# WS2812B.net
KiCad netlist of a schematic drawn in Altium Designer
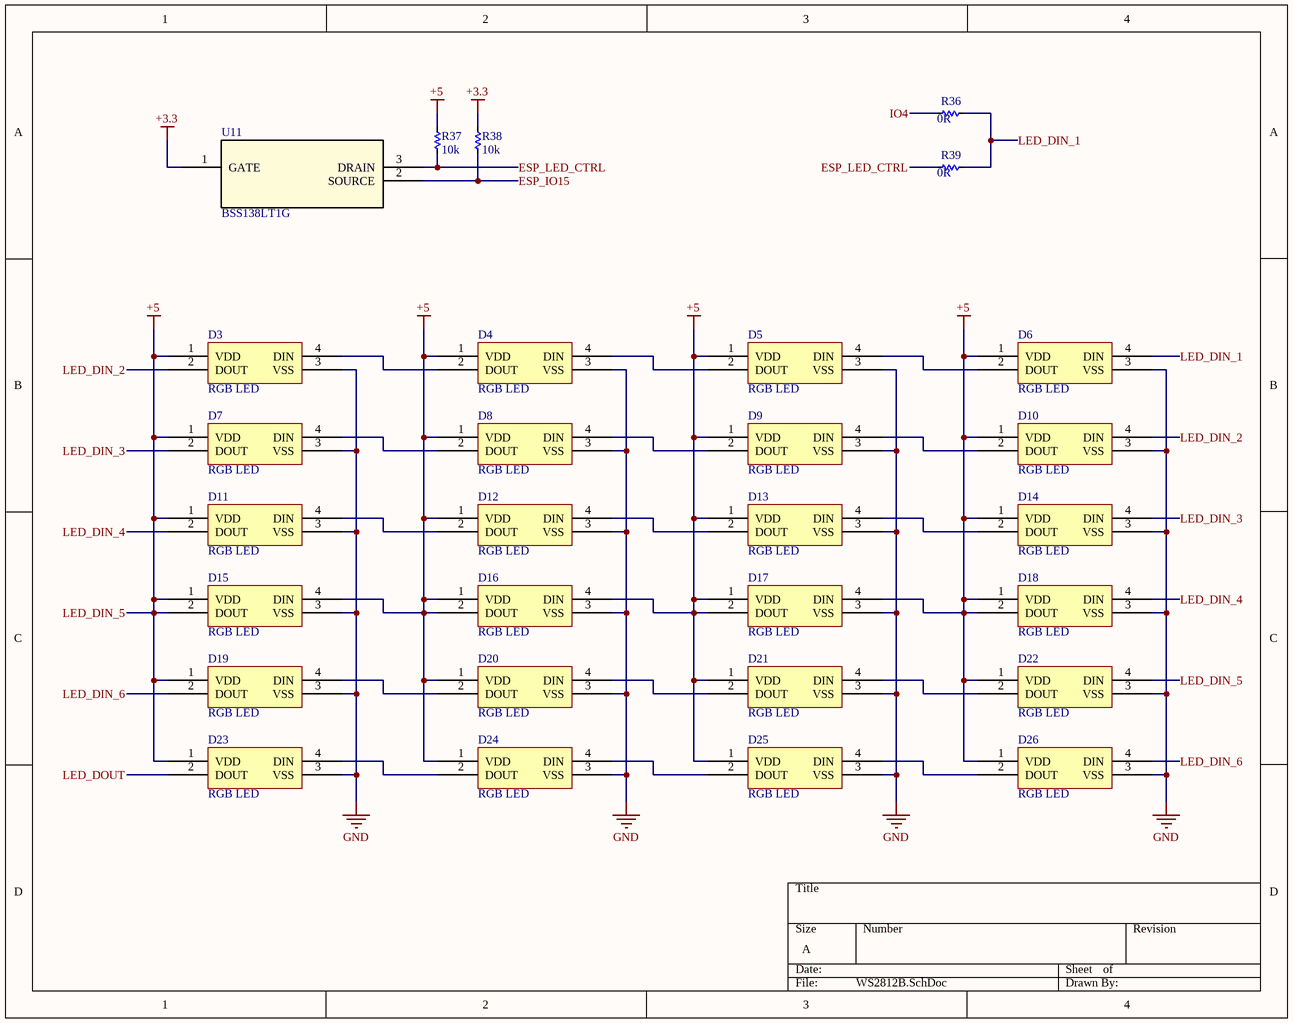
[diagram p0: WS2812B.SchDoc]

(export (version "E")
  (design (tool "Eeschema 10.0.6"))
  (components
    (comp (ref "D3")
      (value "RGB LED")
      (footprint "WS2812B")
      (description "RGB 620~630nm Red, 515~530nm Green, 465~475nm Blue SMD,5x5mm Light Emitting Diodes (LED) ROHS")
      (fields (field (name "MANUFACTURER") "Worldsemi"))
      (libsource (lib "WS2812B") (part "WS2812B"))
    )
    (comp (ref "D4")
      (value "RGB LED")
      (footprint "WS2812B")
      (description "RGB 620~630nm Red, 515~530nm Green, 465~475nm Blue SMD,5x5mm Light Emitting Diodes (LED) ROHS")
      (fields (field (name "MANUFACTURER") "Worldsemi"))
      (libsource (lib "WS2812B") (part "WS2812B"))
    )
    (comp (ref "D5")
      (value "RGB LED")
      (footprint "WS2812B")
      (description "RGB 620~630nm Red, 515~530nm Green, 465~475nm Blue SMD,5x5mm Light Emitting Diodes (LED) ROHS")
      (fields (field (name "MANUFACTURER") "Worldsemi"))
      (libsource (lib "WS2812B") (part "WS2812B"))
    )
    (comp (ref "D6")
      (value "RGB LED")
      (footprint "WS2812B")
      (description "RGB 620~630nm Red, 515~530nm Green, 465~475nm Blue SMD,5x5mm Light Emitting Diodes (LED) ROHS")
      (fields (field (name "MANUFACTURER") "Worldsemi"))
      (libsource (lib "WS2812B") (part "WS2812B"))
    )
    (comp (ref "D7")
      (value "RGB LED")
      (footprint "WS2812B")
      (description "RGB 620~630nm Red, 515~530nm Green, 465~475nm Blue SMD,5x5mm Light Emitting Diodes (LED) ROHS")
      (fields (field (name "MANUFACTURER") "Worldsemi"))
      (libsource (lib "WS2812B") (part "WS2812B"))
    )
    (comp (ref "D8")
      (value "RGB LED")
      (footprint "WS2812B")
      (description "RGB 620~630nm Red, 515~530nm Green, 465~475nm Blue SMD,5x5mm Light Emitting Diodes (LED) ROHS")
      (fields (field (name "MANUFACTURER") "Worldsemi"))
      (libsource (lib "WS2812B") (part "WS2812B"))
    )
    (comp (ref "D9")
      (value "RGB LED")
      (footprint "WS2812B")
      (description "RGB 620~630nm Red, 515~530nm Green, 465~475nm Blue SMD,5x5mm Light Emitting Diodes (LED) ROHS")
      (fields (field (name "MANUFACTURER") "Worldsemi"))
      (libsource (lib "WS2812B") (part "WS2812B"))
    )
    (comp (ref "D10")
      (value "RGB LED")
      (footprint "WS2812B")
      (description "RGB 620~630nm Red, 515~530nm Green, 465~475nm Blue SMD,5x5mm Light Emitting Diodes (LED) ROHS")
      (fields (field (name "MANUFACTURER") "Worldsemi"))
      (libsource (lib "WS2812B") (part "WS2812B"))
    )
    (comp (ref "D11")
      (value "RGB LED")
      (footprint "WS2812B")
      (description "RGB 620~630nm Red, 515~530nm Green, 465~475nm Blue SMD,5x5mm Light Emitting Diodes (LED) ROHS")
      (fields (field (name "MANUFACTURER") "Worldsemi"))
      (libsource (lib "WS2812B") (part "WS2812B"))
    )
    (comp (ref "D12")
      (value "RGB LED")
      (footprint "WS2812B")
      (description "RGB 620~630nm Red, 515~530nm Green, 465~475nm Blue SMD,5x5mm Light Emitting Diodes (LED) ROHS")
      (fields (field (name "MANUFACTURER") "Worldsemi"))
      (libsource (lib "WS2812B") (part "WS2812B"))
    )
    (comp (ref "D13")
      (value "RGB LED")
      (footprint "WS2812B")
      (description "RGB 620~630nm Red, 515~530nm Green, 465~475nm Blue SMD,5x5mm Light Emitting Diodes (LED) ROHS")
      (fields (field (name "MANUFACTURER") "Worldsemi"))
      (libsource (lib "WS2812B") (part "WS2812B"))
    )
    (comp (ref "D14")
      (value "RGB LED")
      (footprint "WS2812B")
      (description "RGB 620~630nm Red, 515~530nm Green, 465~475nm Blue SMD,5x5mm Light Emitting Diodes (LED) ROHS")
      (fields (field (name "MANUFACTURER") "Worldsemi"))
      (libsource (lib "WS2812B") (part "WS2812B"))
    )
    (comp (ref "D15")
      (value "RGB LED")
      (footprint "WS2812B")
      (description "RGB 620~630nm Red, 515~530nm Green, 465~475nm Blue SMD,5x5mm Light Emitting Diodes (LED) ROHS")
      (fields (field (name "MANUFACTURER") "Worldsemi"))
      (libsource (lib "WS2812B") (part "WS2812B"))
    )
    (comp (ref "D16")
      (value "RGB LED")
      (footprint "WS2812B")
      (description "RGB 620~630nm Red, 515~530nm Green, 465~475nm Blue SMD,5x5mm Light Emitting Diodes (LED) ROHS")
      (fields (field (name "MANUFACTURER") "Worldsemi"))
      (libsource (lib "WS2812B") (part "WS2812B"))
    )
    (comp (ref "D17")
      (value "RGB LED")
      (footprint "WS2812B")
      (description "RGB 620~630nm Red, 515~530nm Green, 465~475nm Blue SMD,5x5mm Light Emitting Diodes (LED) ROHS")
      (fields (field (name "MANUFACTURER") "Worldsemi"))
      (libsource (lib "WS2812B") (part "WS2812B"))
    )
    (comp (ref "D18")
      (value "RGB LED")
      (footprint "WS2812B")
      (description "RGB 620~630nm Red, 515~530nm Green, 465~475nm Blue SMD,5x5mm Light Emitting Diodes (LED) ROHS")
      (fields (field (name "MANUFACTURER") "Worldsemi"))
      (libsource (lib "WS2812B") (part "WS2812B"))
    )
    (comp (ref "D19")
      (value "RGB LED")
      (footprint "WS2812B")
      (description "RGB 620~630nm Red, 515~530nm Green, 465~475nm Blue SMD,5x5mm Light Emitting Diodes (LED) ROHS")
      (fields (field (name "MANUFACTURER") "Worldsemi"))
      (libsource (lib "WS2812B") (part "WS2812B"))
    )
    (comp (ref "D20")
      (value "RGB LED")
      (footprint "WS2812B")
      (description "RGB 620~630nm Red, 515~530nm Green, 465~475nm Blue SMD,5x5mm Light Emitting Diodes (LED) ROHS")
      (fields (field (name "MANUFACTURER") "Worldsemi"))
      (libsource (lib "WS2812B") (part "WS2812B"))
    )
    (comp (ref "D21")
      (value "RGB LED")
      (footprint "WS2812B")
      (description "RGB 620~630nm Red, 515~530nm Green, 465~475nm Blue SMD,5x5mm Light Emitting Diodes (LED) ROHS")
      (fields (field (name "MANUFACTURER") "Worldsemi"))
      (libsource (lib "WS2812B") (part "WS2812B"))
    )
    (comp (ref "D22")
      (value "RGB LED")
      (footprint "WS2812B")
      (description "RGB 620~630nm Red, 515~530nm Green, 465~475nm Blue SMD,5x5mm Light Emitting Diodes (LED) ROHS")
      (fields (field (name "MANUFACTURER") "Worldsemi"))
      (libsource (lib "WS2812B") (part "WS2812B"))
    )
    (comp (ref "D23")
      (value "RGB LED")
      (footprint "WS2812B")
      (description "RGB 620~630nm Red, 515~530nm Green, 465~475nm Blue SMD,5x5mm Light Emitting Diodes (LED) ROHS")
      (fields (field (name "MANUFACTURER") "Worldsemi"))
      (libsource (lib "WS2812B") (part "WS2812B"))
    )
    (comp (ref "D24")
      (value "RGB LED")
      (footprint "WS2812B")
      (description "RGB 620~630nm Red, 515~530nm Green, 465~475nm Blue SMD,5x5mm Light Emitting Diodes (LED) ROHS")
      (fields (field (name "MANUFACTURER") "Worldsemi"))
      (libsource (lib "WS2812B") (part "WS2812B"))
    )
    (comp (ref "D25")
      (value "RGB LED")
      (footprint "WS2812B")
      (description "RGB 620~630nm Red, 515~530nm Green, 465~475nm Blue SMD,5x5mm Light Emitting Diodes (LED) ROHS")
      (fields (field (name "MANUFACTURER") "Worldsemi"))
      (libsource (lib "WS2812B") (part "WS2812B"))
    )
    (comp (ref "D26")
      (value "RGB LED")
      (footprint "WS2812B")
      (description "RGB 620~630nm Red, 515~530nm Green, 465~475nm Blue SMD,5x5mm Light Emitting Diodes (LED) ROHS")
      (fields (field (name "MANUFACTURER") "Worldsemi"))
      (libsource (lib "WS2812B") (part "WS2812B"))
    )
    (comp (ref "R36")
      (value "0R")
      (footprint "RES-SMD-0603")
      (description "Resistor")
      (fields
        (field (name "MANUFACTURER") "Generic Components")
        (field (name "Comment") "Res")
        (field (name "PUBLISHER") "Altium Hobart Technology Centre")
      )
      (libsource (lib "LIBRARY") (part "Res-SMD"))
    )
    (comp (ref "R37")
      (value "10k")
      (footprint "RES-SMD-0603")
      (description "Resistor")
      (fields
        (field (name "MANUFACTURER") "Generic Components")
        (field (name "Comment") "Res")
        (field (name "PUBLISHER") "Altium Hobart Technology Centre")
      )
      (libsource (lib "LIBRARY") (part "Res-SMD"))
    )
    (comp (ref "R38")
      (value "10k")
      (footprint "RES-SMD-0603")
      (description "Resistor")
      (fields
        (field (name "MANUFACTURER") "Generic Components")
        (field (name "Comment") "Res")
        (field (name "PUBLISHER") "Altium Hobart Technology Centre")
      )
      (libsource (lib "LIBRARY") (part "Res-SMD"))
    )
    (comp (ref "R39")
      (value "0R")
      (footprint "RES-SMD-0603")
      (description "Resistor")
      (fields
        (field (name "MANUFACTURER") "Generic Components")
        (field (name "Comment") "Res")
        (field (name "PUBLISHER") "Altium Hobart Technology Centre")
      )
      (libsource (lib "LIBRARY") (part "Res-SMD"))
    )
    (comp (ref "U11")
      (value "BSS138LT1G")
      (footprint "SOT23-3_ONS")
      (description "No Description Available")
      (fields (field (name "COPYRIGHT") "Copyright (C) 2018 Accelerated Designs. All rights reserved"))
      (libsource (lib "BSS138LT1G") (part "BSS138LT1G"))
    )
  )
  (nets
    (net (code "1") (name "+3.3") (class "Default")
      (node (ref "R38") (pin "1") (pinfunction "1_1") (pintype "passive"))
      (node (ref "U11") (pin "1") (pinfunction "GATE_1") (pintype "passive"))
    )
    (net (code "2") (name "+5") (class "Default")
      (node (ref "D10") (pin "1") (pinfunction "VDD_1") (pintype "passive"))
      (node (ref "D11") (pin "1") (pinfunction "VDD_1") (pintype "passive"))
      (node (ref "D12") (pin "1") (pinfunction "VDD_1") (pintype "passive"))
      (node (ref "D13") (pin "1") (pinfunction "VDD_1") (pintype "passive"))
      (node (ref "D14") (pin "1") (pinfunction "VDD_1") (pintype "passive"))
      (node (ref "D15") (pin "1") (pinfunction "VDD_1") (pintype "passive"))
      (node (ref "D15") (pin "2") (pinfunction "DOUT_2") (pintype "passive"))
      (node (ref "D15") (pin "4") (pinfunction "DIN_4") (pintype "passive"))
      (node (ref "D16") (pin "1") (pinfunction "VDD_1") (pintype "passive"))
      (node (ref "D16") (pin "2") (pinfunction "DOUT_2") (pintype "passive"))
      (node (ref "D16") (pin "4") (pinfunction "DIN_4") (pintype "passive"))
      (node (ref "D17") (pin "1") (pinfunction "VDD_1") (pintype "passive"))
      (node (ref "D17") (pin "2") (pinfunction "DOUT_2") (pintype "passive"))
      (node (ref "D17") (pin "4") (pinfunction "DIN_4") (pintype "passive"))
      (node (ref "D18") (pin "1") (pinfunction "VDD_1") (pintype "passive"))
      (node (ref "D18") (pin "2") (pinfunction "DOUT_2") (pintype "passive"))
      (node (ref "D19") (pin "1") (pinfunction "VDD_1") (pintype "passive"))
      (node (ref "D20") (pin "1") (pinfunction "VDD_1") (pintype "passive"))
      (node (ref "D21") (pin "1") (pinfunction "VDD_1") (pintype "passive"))
      (node (ref "D22") (pin "1") (pinfunction "VDD_1") (pintype "passive"))
      (node (ref "D22") (pin "4") (pinfunction "DIN_4") (pintype "passive"))
      (node (ref "D23") (pin "1") (pinfunction "VDD_1") (pintype "passive"))
      (node (ref "D24") (pin "1") (pinfunction "VDD_1") (pintype "passive"))
      (node (ref "D25") (pin "1") (pinfunction "VDD_1") (pintype "passive"))
      (node (ref "D26") (pin "1") (pinfunction "VDD_1") (pintype "passive"))
      (node (ref "D3") (pin "1") (pinfunction "VDD_1") (pintype "passive"))
      (node (ref "D4") (pin "1") (pinfunction "VDD_1") (pintype "passive"))
      (node (ref "D5") (pin "1") (pinfunction "VDD_1") (pintype "passive"))
      (node (ref "D6") (pin "1") (pinfunction "VDD_1") (pintype "passive"))
      (node (ref "D7") (pin "1") (pinfunction "VDD_1") (pintype "passive"))
      (node (ref "D8") (pin "1") (pinfunction "VDD_1") (pintype "passive"))
      (node (ref "D9") (pin "1") (pinfunction "VDD_1") (pintype "passive"))
      (node (ref "R37") (pin "1") (pinfunction "1_1") (pintype "passive"))
    )
    (net (code "3") (name "/ESP_IO15") (class "Default")
      (node (ref "R38") (pin "2") (pinfunction "2_2") (pintype "passive"))
      (node (ref "U11") (pin "2") (pinfunction "SOURCE_2") (pintype "passive"))
    )
    (net (code "4") (name "/ESP_LED_CTRL") (class "Default")
      (node (ref "R37") (pin "2") (pinfunction "2_2") (pintype "passive"))
      (node (ref "R39") (pin "2") (pinfunction "2_2") (pintype "passive"))
      (node (ref "U11") (pin "3") (pinfunction "DRAIN_3") (pintype "passive"))
    )
    (net (code "5") (name "/IO4") (class "Default")
      (node (ref "R36") (pin "2") (pinfunction "2_2") (pintype "passive"))
    )
    (net (code "6") (name "/LED_DIN_1") (class "Default")
      (node (ref "D6") (pin "4") (pinfunction "DIN_4") (pintype "passive"))
      (node (ref "R36") (pin "1") (pinfunction "1_1") (pintype "passive"))
      (node (ref "R39") (pin "1") (pinfunction "1_1") (pintype "passive"))
    )
    (net (code "7") (name "/LED_DIN_2") (class "Default")
      (node (ref "D10") (pin "4") (pinfunction "DIN_4") (pintype "passive"))
      (node (ref "D3") (pin "2") (pinfunction "DOUT_2") (pintype "passive"))
    )
    (net (code "8") (name "/LED_DIN_3") (class "Default")
      (node (ref "D14") (pin "4") (pinfunction "DIN_4") (pintype "passive"))
      (node (ref "D7") (pin "2") (pinfunction "DOUT_2") (pintype "passive"))
    )
    (net (code "9") (name "/LED_DIN_4") (class "Default")
      (node (ref "D11") (pin "2") (pinfunction "DOUT_2") (pintype "passive"))
      (node (ref "D18") (pin "4") (pinfunction "DIN_4") (pintype "passive"))
    )
    (net (code "10") (name "/LED_DIN_6") (class "Default")
      (node (ref "D19") (pin "2") (pinfunction "DOUT_2") (pintype "passive"))
      (node (ref "D26") (pin "4") (pinfunction "DIN_4") (pintype "passive"))
    )
    (net (code "11") (name "/LED_DOUT") (class "Default")
      (node (ref "D23") (pin "2") (pinfunction "DOUT_2") (pintype "passive"))
    )
    (net (code "12") (name "GND") (class "Default")
      (node (ref "D10") (pin "3") (pinfunction "VSS_3") (pintype "passive"))
      (node (ref "D11") (pin "3") (pinfunction "VSS_3") (pintype "passive"))
      (node (ref "D12") (pin "3") (pinfunction "VSS_3") (pintype "passive"))
      (node (ref "D13") (pin "3") (pinfunction "VSS_3") (pintype "passive"))
      (node (ref "D14") (pin "3") (pinfunction "VSS_3") (pintype "passive"))
      (node (ref "D15") (pin "3") (pinfunction "VSS_3") (pintype "passive"))
      (node (ref "D16") (pin "3") (pinfunction "VSS_3") (pintype "passive"))
      (node (ref "D17") (pin "3") (pinfunction "VSS_3") (pintype "passive"))
      (node (ref "D18") (pin "3") (pinfunction "VSS_3") (pintype "passive"))
      (node (ref "D19") (pin "3") (pinfunction "VSS_3") (pintype "passive"))
      (node (ref "D20") (pin "3") (pinfunction "VSS_3") (pintype "passive"))
      (node (ref "D21") (pin "3") (pinfunction "VSS_3") (pintype "passive"))
      (node (ref "D22") (pin "3") (pinfunction "VSS_3") (pintype "passive"))
      (node (ref "D23") (pin "3") (pinfunction "VSS_3") (pintype "passive"))
      (node (ref "D24") (pin "3") (pinfunction "VSS_3") (pintype "passive"))
      (node (ref "D25") (pin "3") (pinfunction "VSS_3") (pintype "passive"))
      (node (ref "D26") (pin "3") (pinfunction "VSS_3") (pintype "passive"))
      (node (ref "D3") (pin "3") (pinfunction "VSS_3") (pintype "passive"))
      (node (ref "D4") (pin "3") (pinfunction "VSS_3") (pintype "passive"))
      (node (ref "D5") (pin "3") (pinfunction "VSS_3") (pintype "passive"))
      (node (ref "D6") (pin "3") (pinfunction "VSS_3") (pintype "passive"))
      (node (ref "D7") (pin "3") (pinfunction "VSS_3") (pintype "passive"))
      (node (ref "D8") (pin "3") (pinfunction "VSS_3") (pintype "passive"))
      (node (ref "D9") (pin "3") (pinfunction "VSS_3") (pintype "passive"))
    )
    (net (code "13") (name "Net-(D3-DIN)") (class "Default")
      (node (ref "D3") (pin "4") (pinfunction "DIN_4") (pintype "passive"))
      (node (ref "D4") (pin "2") (pinfunction "DOUT_2") (pintype "passive"))
    )
    (net (code "14") (name "Net-(D4-DIN)") (class "Default")
      (node (ref "D4") (pin "4") (pinfunction "DIN_4") (pintype "passive"))
      (node (ref "D5") (pin "2") (pinfunction "DOUT_2") (pintype "passive"))
    )
    (net (code "15") (name "Net-(D5-DIN)") (class "Default")
      (node (ref "D5") (pin "4") (pinfunction "DIN_4") (pintype "passive"))
      (node (ref "D6") (pin "2") (pinfunction "DOUT_2") (pintype "passive"))
    )
    (net (code "16") (name "Net-(D7-DIN)") (class "Default")
      (node (ref "D7") (pin "4") (pinfunction "DIN_4") (pintype "passive"))
      (node (ref "D8") (pin "2") (pinfunction "DOUT_2") (pintype "passive"))
    )
    (net (code "17") (name "Net-(D8-DIN)") (class "Default")
      (node (ref "D8") (pin "4") (pinfunction "DIN_4") (pintype "passive"))
      (node (ref "D9") (pin "2") (pinfunction "DOUT_2") (pintype "passive"))
    )
    (net (code "18") (name "Net-(D10-DOUT)") (class "Default")
      (node (ref "D10") (pin "2") (pinfunction "DOUT_2") (pintype "passive"))
      (node (ref "D9") (pin "4") (pinfunction "DIN_4") (pintype "passive"))
    )
    (net (code "19") (name "Net-(D11-DIN)") (class "Default")
      (node (ref "D11") (pin "4") (pinfunction "DIN_4") (pintype "passive"))
      (node (ref "D12") (pin "2") (pinfunction "DOUT_2") (pintype "passive"))
    )
    (net (code "20") (name "Net-(D12-DIN)") (class "Default")
      (node (ref "D12") (pin "4") (pinfunction "DIN_4") (pintype "passive"))
      (node (ref "D13") (pin "2") (pinfunction "DOUT_2") (pintype "passive"))
    )
    (net (code "21") (name "Net-(D13-DIN)") (class "Default")
      (node (ref "D13") (pin "4") (pinfunction "DIN_4") (pintype "passive"))
      (node (ref "D14") (pin "2") (pinfunction "DOUT_2") (pintype "passive"))
    )
    (net (code "22") (name "Net-(D19-DIN)") (class "Default")
      (node (ref "D19") (pin "4") (pinfunction "DIN_4") (pintype "passive"))
      (node (ref "D20") (pin "2") (pinfunction "DOUT_2") (pintype "passive"))
    )
    (net (code "23") (name "Net-(D20-DIN)") (class "Default")
      (node (ref "D20") (pin "4") (pinfunction "DIN_4") (pintype "passive"))
      (node (ref "D21") (pin "2") (pinfunction "DOUT_2") (pintype "passive"))
    )
    (net (code "24") (name "Net-(D21-DIN)") (class "Default")
      (node (ref "D21") (pin "4") (pinfunction "DIN_4") (pintype "passive"))
      (node (ref "D22") (pin "2") (pinfunction "DOUT_2") (pintype "passive"))
    )
    (net (code "25") (name "Net-(D23-DIN)") (class "Default")
      (node (ref "D23") (pin "4") (pinfunction "DIN_4") (pintype "passive"))
      (node (ref "D24") (pin "2") (pinfunction "DOUT_2") (pintype "passive"))
    )
    (net (code "26") (name "Net-(D24-DIN)") (class "Default")
      (node (ref "D24") (pin "4") (pinfunction "DIN_4") (pintype "passive"))
      (node (ref "D25") (pin "2") (pinfunction "DOUT_2") (pintype "passive"))
    )
    (net (code "27") (name "Net-(D25-DIN)") (class "Default")
      (node (ref "D25") (pin "4") (pinfunction "DIN_4") (pintype "passive"))
      (node (ref "D26") (pin "2") (pinfunction "DOUT_2") (pintype "passive"))
    )
  )
)
